# V1_0.net
KiCad netlist of a schematic drawn in Altium Designer
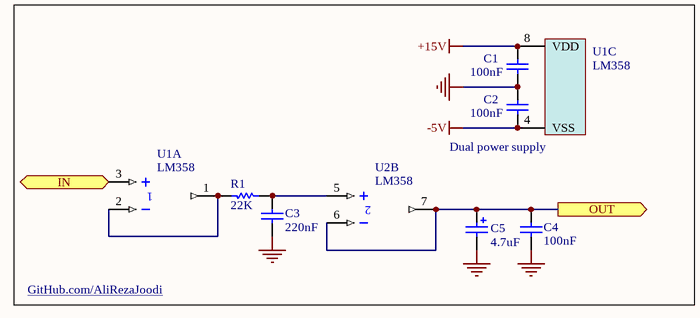
[diagram p0: V1.0.SchDoc]

(export (version "E")
  (design (tool "Eeschema 10.0.6"))
  (components
    (comp (ref "C1")
      (value "100nF")
      (footprint "CAPNTO2.54-3.05x1.78A")
      (description "Capacitor")
      (fields (field (name "MANUFACTURER") "Generic Components") (field (name "PUBLISHER") "Altium Limited"))
      (libsource (lib "Miscellaneous Devices") (part "Cap"))
    )
    (comp (ref "C2")
      (value "100nF")
      (footprint "CAPNTO2.54-3.05x1.78A")
      (description "Capacitor")
      (fields (field (name "MANUFACTURER") "Generic Components") (field (name "PUBLISHER") "Altium Limited"))
      (libsource (lib "Miscellaneous Devices") (part "Cap"))
    )
    (comp (ref "C3")
      (value "220nF")
      (footprint "CAPNTO5.08-7.37x3.94")
      (description "Capacitor")
      (fields (field (name "PUBLISHER") "Altium Limited"))
      (libsource (lib "Miscellaneous Devices") (part "Cap"))
    )
    (comp (ref "C4")
      (value "100nF")
      (footprint "CAPNTO2.54-3.05x1.78A")
      (description "Capacitor")
      (fields (field (name "MANUFACTURER") "Generic Components") (field (name "PUBLISHER") "Altium Limited"))
      (libsource (lib "Miscellaneous Devices") (part "Cap"))
    )
    (comp (ref "C5")
      (value "4.7uF")
      (footprint "CAPPR2.5-6.3x5")
      (description "Polarized Capacitor (Radial)")
      (fields (field (name "MANUFACTURER") "Generic Components") (field (name "PUBLISHER") "Altium Limited"))
      (libsource (lib "Miscellaneous Devices") (part "Cap Pol1"))
    )
    (comp (ref "R1")
      (value "22K")
      (footprint "AXIAL-0.4")
      (description "Resistor")
      (fields (field (name "PUBLISHER") "Altium Limited"))
      (libsource (lib "Miscellaneous Devices") (part "Res1"))
    )
    (comp (ref "U1")
      (value "LM358")
      (footprint "751-02_L")
      (description "Dual Low-Power Operational Amplifier")
      (fields (field (name "PUBLISHER") "Altium Limited"))
      (libsource (lib "my Libraries") (part "LM358"))
    )
    (comp (ref "U2")
      (value "LM358")
      (footprint "751-02_L")
      (description "Dual Low-Power Operational Amplifier")
      (fields (field (name "PUBLISHER") "Altium Limited"))
      (libsource (lib "my Libraries") (part "LM358"))
    )
  )
  (nets
    (net (code "1") (name "+15V") (class "Default")
      (node (ref "C1") (pin "2") (pinfunction "2_2") (pintype "passive"))
      (node (ref "U1") (pin "8") (pinfunction "VDD_8") (pintype "passive"))
    )
    (net (code "2") (name "-5V") (class "Default")
      (node (ref "C2") (pin "1") (pinfunction "1_1") (pintype "passive"))
      (node (ref "U1") (pin "4") (pinfunction "VSS_4") (pintype "power_in"))
    )
    (net (code "3") (name "/IN") (class "Default")
      (node (ref "U1") (pin "3") (pinfunction "IN+_3") (pintype "input"))
    )
    (net (code "4") (name "/OUT") (class "Default")
      (node (ref "C4") (pin "2") (pinfunction "2_2") (pintype "passive"))
      (node (ref "C5") (pin "1") (pinfunction "1_1") (pintype "passive"))
      (node (ref "U2") (pin "6") (pinfunction "IN-_6") (pintype "input"))
      (node (ref "U2") (pin "7") (pinfunction "OUT_7") (pintype "output"))
    )
    (net (code "5") (name "GND") (class "Default")
      (node (ref "C1") (pin "1") (pinfunction "1_1") (pintype "passive"))
      (node (ref "C2") (pin "2") (pinfunction "2_2") (pintype "passive"))
      (node (ref "C3") (pin "1") (pinfunction "1_1") (pintype "passive"))
      (node (ref "C4") (pin "1") (pinfunction "1_1") (pintype "passive"))
      (node (ref "C5") (pin "2") (pinfunction "2_2") (pintype "passive"))
    )
    (net (code "6") (name "Net-(U1A-IN-)") (class "Default")
      (node (ref "R1") (pin "2") (pinfunction "2_2") (pintype "passive"))
      (node (ref "U1") (pin "1") (pinfunction "OUT_1") (pintype "output"))
      (node (ref "U1") (pin "2") (pinfunction "IN-_2") (pintype "input"))
    )
    (net (code "7") (name "Net-(U2B-IN+)") (class "Default")
      (node (ref "C3") (pin "2") (pinfunction "2_2") (pintype "passive"))
      (node (ref "R1") (pin "1") (pinfunction "1_1") (pintype "passive"))
      (node (ref "U2") (pin "5") (pinfunction "IN+_5") (pintype "input"))
    )
  )
)
